# untitled.net
KiCad netlist of a schematic drawn in EAGLE
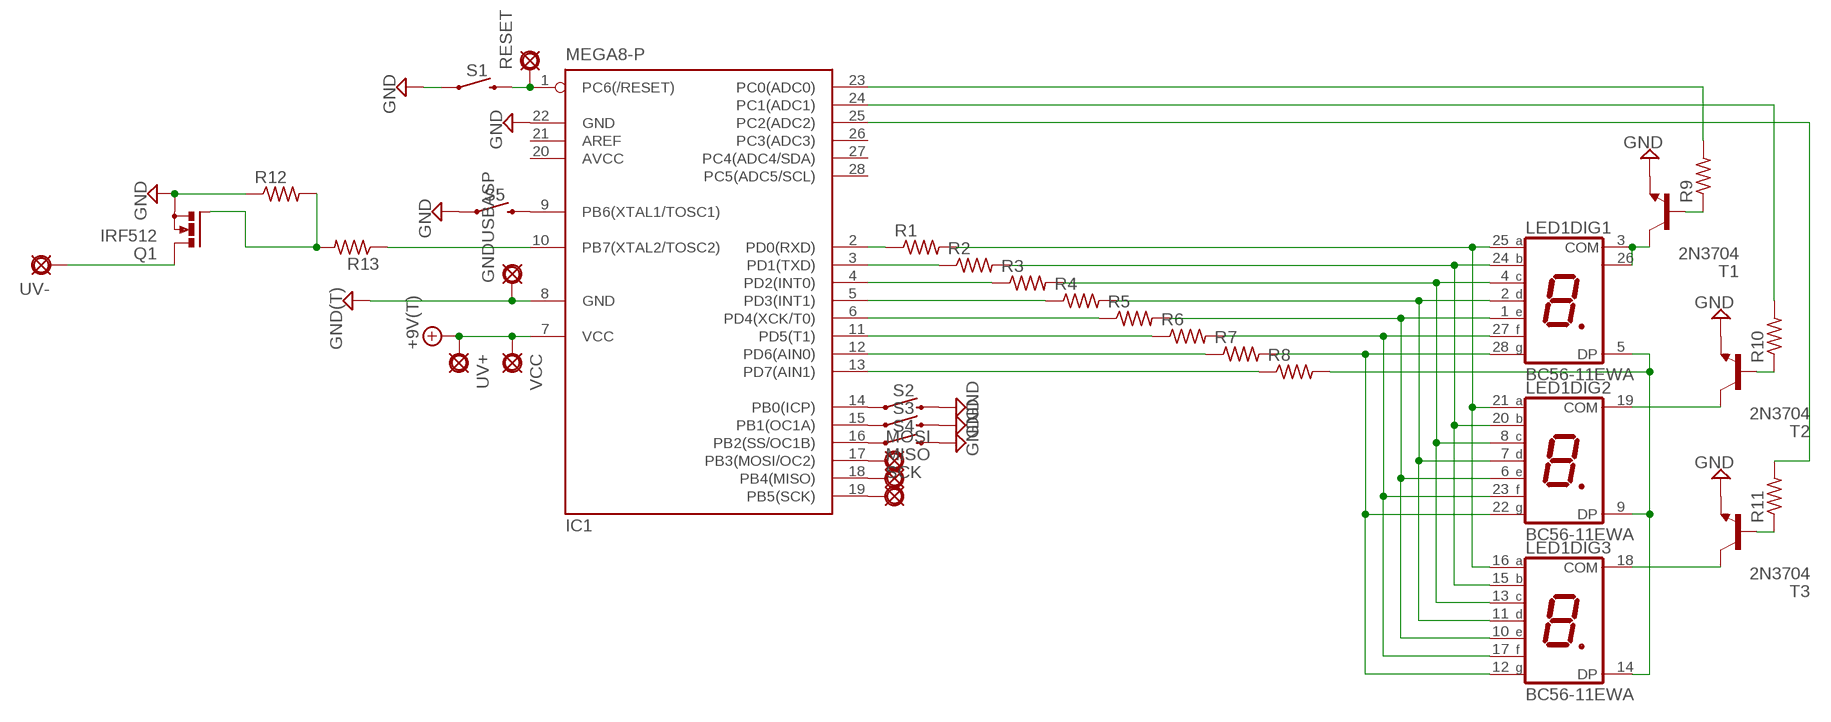
[diagram p0: schematic, sheet 1]

(export (version "E")
  (design (tool "Eeschema 10.0.6"))
  (components
    (comp (ref "+9V1")
      (value "+9V(T)")
      (footprint "eagle-import:SQUARE")
      (libsource (lib "eagle-import") (part "+9V(T)"))
    )
    (comp (ref "GND1")
      (value "GND(T)")
      (footprint "eagle-import:SQUARE")
      (libsource (lib "eagle-import") (part "GND(T)"))
    )
    (comp (ref "GNDUSBASP")
      (value "PAD")
      (footprint "eagle-import:SQUARE")
      (libsource (lib "eagle-import") (part "PAD"))
    )
    (comp (ref "IC1")
      (value "MEGA8-P")
      (footprint "eagle-import:DIL28-3")
      (libsource (lib "eagle-import") (part "MEGA8-P"))
    )
    (comp (ref "LED1")
      (value "BC56-11EWA")
      (footprint "eagle-import:BA_BC56")
      (libsource (lib "eagle-import") (part "B?56-11WACE"))
    )
    (comp (ref "MISO")
      (value "PAD")
      (footprint "eagle-import:SQUARE")
      (libsource (lib "eagle-import") (part "PAD"))
    )
    (comp (ref "MOSI")
      (value "PAD")
      (footprint "eagle-import:SQUARE")
      (libsource (lib "eagle-import") (part "PAD"))
    )
    (comp (ref "Q1")
      (value "IRF512")
      (footprint "eagle-import:TO220BV")
      (libsource (lib "eagle-import") (part "IRF512"))
    )
    (comp (ref "R1")
      (value "6MM.3")
      (footprint "eagle-import:R0207_3")
      (libsource (lib "eagle-import") (part "6MM.3"))
    )
    (comp (ref "R2")
      (value "6MM.3")
      (footprint "eagle-import:R0207_3")
      (libsource (lib "eagle-import") (part "6MM.3"))
    )
    (comp (ref "R3")
      (value "6MM.3")
      (footprint "eagle-import:R0207_3")
      (libsource (lib "eagle-import") (part "6MM.3"))
    )
    (comp (ref "R4")
      (value "6MM.3")
      (footprint "eagle-import:R0207_3")
      (libsource (lib "eagle-import") (part "6MM.3"))
    )
    (comp (ref "R5")
      (value "6MM.3")
      (footprint "eagle-import:R0207_3")
      (libsource (lib "eagle-import") (part "6MM.3"))
    )
    (comp (ref "R6")
      (value "6MM.3")
      (footprint "eagle-import:R0207_3")
      (libsource (lib "eagle-import") (part "6MM.3"))
    )
    (comp (ref "R7")
      (value "6MM.3")
      (footprint "eagle-import:R0207_3")
      (libsource (lib "eagle-import") (part "6MM.3"))
    )
    (comp (ref "R8")
      (value "6MM.3")
      (footprint "eagle-import:R0207_3")
      (libsource (lib "eagle-import") (part "6MM.3"))
    )
    (comp (ref "R9")
      (value "6MM.3")
      (footprint "eagle-import:R0207_3")
      (libsource (lib "eagle-import") (part "6MM.3"))
    )
    (comp (ref "R10")
      (value "6MM.3")
      (footprint "eagle-import:R0207_3")
      (libsource (lib "eagle-import") (part "6MM.3"))
    )
    (comp (ref "R11")
      (value "6MM.3")
      (footprint "eagle-import:R0207_3")
      (libsource (lib "eagle-import") (part "6MM.3"))
    )
    (comp (ref "R12")
      (value "6MM.3")
      (footprint "eagle-import:R0207_3")
      (libsource (lib "eagle-import") (part "6MM.3"))
    )
    (comp (ref "R13")
      (value "6MM.3")
      (footprint "eagle-import:R0207_3")
      (libsource (lib "eagle-import") (part "6MM.3"))
    )
    (comp (ref "RESET")
      (value "PAD")
      (footprint "eagle-import:SQUARE")
      (libsource (lib "eagle-import") (part "PAD"))
    )
    (comp (ref "S1")
      (value "MOMENTARY-SWITCH-SPST-PTH-6.0MM")
      (footprint "eagle-import:TACTILE_SWITCH_PTH_6.0MM")
      (libsource (lib "eagle-import") (part "MOMENTARY-SWITCH-SPST-PTH-6.0MM"))
    )
    (comp (ref "S2")
      (value "MOMENTARY-SWITCH-SPST-PTH-6.0MM")
      (footprint "eagle-import:TACTILE_SWITCH_PTH_6.0MM")
      (libsource (lib "eagle-import") (part "MOMENTARY-SWITCH-SPST-PTH-6.0MM"))
    )
    (comp (ref "S3")
      (value "MOMENTARY-SWITCH-SPST-PTH-6.0MM")
      (footprint "eagle-import:TACTILE_SWITCH_PTH_6.0MM")
      (libsource (lib "eagle-import") (part "MOMENTARY-SWITCH-SPST-PTH-6.0MM"))
    )
    (comp (ref "S4")
      (value "MOMENTARY-SWITCH-SPST-PTH-6.0MM")
      (footprint "eagle-import:TACTILE_SWITCH_PTH_6.0MM")
      (libsource (lib "eagle-import") (part "MOMENTARY-SWITCH-SPST-PTH-6.0MM"))
    )
    (comp (ref "S5")
      (value "MOMENTARY-SWITCH-SPST-PTH-6.0MM")
      (footprint "eagle-import:TACTILE_SWITCH_PTH_6.0MM")
      (libsource (lib "eagle-import") (part "MOMENTARY-SWITCH-SPST-PTH-6.0MM"))
    )
    (comp (ref "SCK")
      (value "PAD")
      (footprint "eagle-import:SQUARE")
      (libsource (lib "eagle-import") (part "PAD"))
    )
    (comp (ref "T1")
      (value "2N3704")
      (footprint "eagle-import:TO92")
      (libsource (lib "eagle-import") (part "2N3704"))
    )
    (comp (ref "T2")
      (value "2N3704")
      (footprint "eagle-import:TO92")
      (libsource (lib "eagle-import") (part "2N3704"))
    )
    (comp (ref "T3")
      (value "2N3704")
      (footprint "eagle-import:TO92")
      (libsource (lib "eagle-import") (part "2N3704"))
    )
    (comp (ref "UV+")
      (value "PAD")
      (footprint "eagle-import:SQUARE")
      (libsource (lib "eagle-import") (part "PAD"))
    )
    (comp (ref "UV-")
      (value "PAD")
      (footprint "eagle-import:SQUARE")
      (libsource (lib "eagle-import") (part "PAD"))
    )
    (comp (ref "VCC")
      (value "PAD")
      (footprint "eagle-import:SQUARE")
      (libsource (lib "eagle-import") (part "PAD"))
    )
  )
  (nets
    (net (code "1") (name "+9V(T)") (class "Default")
      (node (ref "+9V1") (pin "1") (pinfunction "+9V_1") (pintype "power_in"))
      (node (ref "IC1") (pin "7") (pinfunction "VCC_7") (pintype "power_in"))
      (node (ref "UV+") (pin "1") (pinfunction "PAD_1") (pintype "passive"))
      (node (ref "VCC") (pin "1") (pinfunction "PAD_1") (pintype "passive"))
    )
    (net (code "2") (name "/AVCC") (class "Default")
      (node (ref "IC1") (pin "20") (pinfunction "AVCC_20") (pintype "power_in"))
    )
    (net (code "3") (name "GND") (class "Default")
      (node (ref "GND1") (pin "1") (pinfunction "GND_1") (pintype "power_in"))
      (node (ref "GNDUSBASP") (pin "1") (pinfunction "PAD_1") (pintype "passive"))
      (node (ref "IC1") (pin "22") (pinfunction "GND_22") (pintype "power_in"))
      (node (ref "IC1") (pin "8") (pinfunction "GND_8") (pintype "power_in"))
      (node (ref "Q1") (pin "S") (pinfunction "S_S") (pintype "passive"))
      (node (ref "R12") (pin "1") (pinfunction "1_1") (pintype "passive"))
      (node (ref "S1") (pin "1") (pinfunction "1_1") (pintype "passive"))
      (node (ref "S2") (pin "3") (pinfunction "2_3") (pintype "passive"))
      (node (ref "S3") (pin "3") (pinfunction "2_3") (pintype "passive"))
      (node (ref "S4") (pin "3") (pinfunction "2_3") (pintype "passive"))
      (node (ref "S5") (pin "1") (pinfunction "1_1") (pintype "passive"))
      (node (ref "T1") (pin "3") (pinfunction "E_3") (pintype "passive"))
      (node (ref "T2") (pin "3") (pinfunction "E_3") (pintype "passive"))
      (node (ref "T3") (pin "3") (pinfunction "E_3") (pintype "passive"))
    )
    (net (code "4") (name "Net-(IC1-PB0(ICP))") (class "Default")
      (node (ref "IC1") (pin "14") (pinfunction "PB0(ICP)_14") (pintype "bidirectional"))
      (node (ref "S2") (pin "1") (pinfunction "1_1") (pintype "passive"))
    )
    (net (code "5") (name "Net-(IC1-PB1(OC1A))") (class "Default")
      (node (ref "IC1") (pin "15") (pinfunction "PB1(OC1A)_15") (pintype "bidirectional"))
      (node (ref "S3") (pin "1") (pinfunction "1_1") (pintype "passive"))
    )
    (net (code "6") (name "Net-(IC1-PB2(SS{slash}OC1B))") (class "Default")
      (node (ref "IC1") (pin "16") (pinfunction "PB2(SS/OC1B)_16") (pintype "bidirectional"))
      (node (ref "S4") (pin "1") (pinfunction "1_1") (pintype "passive"))
    )
    (net (code "7") (name "Net-(IC1-PB3(MOSI{slash}OC2))") (class "Default")
      (node (ref "IC1") (pin "17") (pinfunction "PB3(MOSI/OC2)_17") (pintype "bidirectional"))
      (node (ref "MOSI") (pin "1") (pinfunction "PAD_1") (pintype "passive"))
    )
    (net (code "8") (name "Net-(IC1-PB4(MISO))") (class "Default")
      (node (ref "IC1") (pin "18") (pinfunction "PB4(MISO)_18") (pintype "bidirectional"))
      (node (ref "MISO") (pin "1") (pinfunction "PAD_1") (pintype "passive"))
    )
    (net (code "9") (name "Net-(IC1-PB5(SCK))") (class "Default")
      (node (ref "IC1") (pin "19") (pinfunction "PB5(SCK)_19") (pintype "bidirectional"))
      (node (ref "SCK") (pin "1") (pinfunction "PAD_1") (pintype "passive"))
    )
    (net (code "10") (name "Net-(IC1-PB6(XTAL1{slash}TOSC1))") (class "Default")
      (node (ref "IC1") (pin "9") (pinfunction "PB6(XTAL1/TOSC1)_9") (pintype "bidirectional"))
      (node (ref "S5") (pin "3") (pinfunction "2_3") (pintype "passive"))
    )
    (net (code "11") (name "Net-(IC1-PB7(XTAL2{slash}TOSC2))") (class "Default")
      (node (ref "IC1") (pin "10") (pinfunction "PB7(XTAL2/TOSC2)_10") (pintype "bidirectional"))
      (node (ref "R13") (pin "1") (pinfunction "1_1") (pintype "passive"))
    )
    (net (code "12") (name "Net-(IC1-PC0(ADC0))") (class "Default")
      (node (ref "IC1") (pin "23") (pinfunction "PC0(ADC0)_23") (pintype "bidirectional"))
      (node (ref "R9") (pin "2") (pinfunction "2_2") (pintype "passive"))
    )
    (net (code "13") (name "Net-(IC1-PC1(ADC1))") (class "Default")
      (node (ref "IC1") (pin "24") (pinfunction "PC1(ADC1)_24") (pintype "bidirectional"))
      (node (ref "R10") (pin "2") (pinfunction "2_2") (pintype "passive"))
    )
    (net (code "14") (name "Net-(IC1-PC2(ADC2))") (class "Default")
      (node (ref "IC1") (pin "25") (pinfunction "PC2(ADC2)_25") (pintype "bidirectional"))
      (node (ref "R11") (pin "2") (pinfunction "2_2") (pintype "passive"))
    )
    (net (code "15") (name "Net-(IC1-PC6({slash}RESET))") (class "Default")
      (node (ref "IC1") (pin "1") (pinfunction "PC6(/RESET)_1") (pintype "bidirectional"))
      (node (ref "RESET") (pin "1") (pinfunction "PAD_1") (pintype "passive"))
      (node (ref "S1") (pin "3") (pinfunction "2_3") (pintype "passive"))
    )
    (net (code "16") (name "Net-(IC1-PD0(RXD))") (class "Default")
      (node (ref "IC1") (pin "2") (pinfunction "PD0(RXD)_2") (pintype "bidirectional"))
      (node (ref "R1") (pin "1") (pinfunction "1_1") (pintype "passive"))
    )
    (net (code "17") (name "Net-(IC1-PD1(TXD))") (class "Default")
      (node (ref "IC1") (pin "3") (pinfunction "PD1(TXD)_3") (pintype "bidirectional"))
      (node (ref "R2") (pin "1") (pinfunction "1_1") (pintype "passive"))
    )
    (net (code "18") (name "Net-(IC1-PD2(INT0))") (class "Default")
      (node (ref "IC1") (pin "4") (pinfunction "PD2(INT0)_4") (pintype "bidirectional"))
      (node (ref "R3") (pin "1") (pinfunction "1_1") (pintype "passive"))
    )
    (net (code "19") (name "Net-(IC1-PD3(INT1))") (class "Default")
      (node (ref "IC1") (pin "5") (pinfunction "PD3(INT1)_5") (pintype "bidirectional"))
      (node (ref "R4") (pin "1") (pinfunction "1_1") (pintype "passive"))
    )
    (net (code "20") (name "Net-(IC1-PD4(XCK{slash}T0))") (class "Default")
      (node (ref "IC1") (pin "6") (pinfunction "PD4(XCK/T0)_6") (pintype "bidirectional"))
      (node (ref "R5") (pin "1") (pinfunction "1_1") (pintype "passive"))
    )
    (net (code "21") (name "Net-(IC1-PD5(T1))") (class "Default")
      (node (ref "IC1") (pin "11") (pinfunction "PD5(T1)_11") (pintype "bidirectional"))
      (node (ref "R6") (pin "1") (pinfunction "1_1") (pintype "passive"))
    )
    (net (code "22") (name "Net-(IC1-PD6(AIN0))") (class "Default")
      (node (ref "IC1") (pin "12") (pinfunction "PD6(AIN0)_12") (pintype "bidirectional"))
      (node (ref "R7") (pin "1") (pinfunction "1_1") (pintype "passive"))
    )
    (net (code "23") (name "Net-(IC1-PD7(AIN1))") (class "Default")
      (node (ref "IC1") (pin "13") (pinfunction "PD7(AIN1)_13") (pintype "bidirectional"))
      (node (ref "R8") (pin "1") (pinfunction "1_1") (pintype "passive"))
    )
    (net (code "24") (name "Net-(LED1A-A)") (class "Default")
      (node (ref "LED1") (pin "16") (pinfunction "A_16") (pintype "passive"))
      (node (ref "LED1") (pin "21") (pinfunction "A_21") (pintype "passive"))
      (node (ref "LED1") (pin "25") (pinfunction "A_25") (pintype "passive"))
      (node (ref "R1") (pin "2") (pinfunction "2_2") (pintype "passive"))
    )
    (net (code "25") (name "Net-(LED1A-B)") (class "Default")
      (node (ref "LED1") (pin "15") (pinfunction "B_15") (pintype "passive"))
      (node (ref "LED1") (pin "20") (pinfunction "B_20") (pintype "passive"))
      (node (ref "LED1") (pin "24") (pinfunction "B_24") (pintype "passive"))
      (node (ref "R2") (pin "2") (pinfunction "2_2") (pintype "passive"))
    )
    (net (code "26") (name "Net-(LED1A-C)") (class "Default")
      (node (ref "LED1") (pin "13") (pinfunction "C_13") (pintype "passive"))
      (node (ref "LED1") (pin "4") (pinfunction "C_4") (pintype "passive"))
      (node (ref "LED1") (pin "8") (pinfunction "C_8") (pintype "passive"))
      (node (ref "R3") (pin "2") (pinfunction "2_2") (pintype "passive"))
    )
    (net (code "27") (name "Net-(LED1A-D)") (class "Default")
      (node (ref "LED1") (pin "11") (pinfunction "D_11") (pintype "passive"))
      (node (ref "LED1") (pin "2") (pinfunction "D_2") (pintype "passive"))
      (node (ref "LED1") (pin "7") (pinfunction "D_7") (pintype "passive"))
      (node (ref "R4") (pin "2") (pinfunction "2_2") (pintype "passive"))
    )
    (net (code "28") (name "Net-(LED1A-DP)") (class "Default")
      (node (ref "LED1") (pin "14") (pinfunction "DP_14") (pintype "passive"))
      (node (ref "LED1") (pin "5") (pinfunction "DP_5") (pintype "passive"))
      (node (ref "LED1") (pin "9") (pinfunction "DP_9") (pintype "passive"))
      (node (ref "R8") (pin "2") (pinfunction "2_2") (pintype "passive"))
    )
    (net (code "29") (name "Net-(LED1A-E)") (class "Default")
      (node (ref "LED1") (pin "1") (pinfunction "E_1") (pintype "passive"))
      (node (ref "LED1") (pin "10") (pinfunction "E_10") (pintype "passive"))
      (node (ref "LED1") (pin "6") (pinfunction "E_6") (pintype "passive"))
      (node (ref "R5") (pin "2") (pinfunction "2_2") (pintype "passive"))
    )
    (net (code "30") (name "Net-(LED1A-F)") (class "Default")
      (node (ref "LED1") (pin "17") (pinfunction "F_17") (pintype "passive"))
      (node (ref "LED1") (pin "23") (pinfunction "F_23") (pintype "passive"))
      (node (ref "LED1") (pin "27") (pinfunction "F_27") (pintype "passive"))
      (node (ref "R6") (pin "2") (pinfunction "2_2") (pintype "passive"))
    )
    (net (code "31") (name "Net-(LED1A-G)") (class "Default")
      (node (ref "LED1") (pin "12") (pinfunction "G_12") (pintype "passive"))
      (node (ref "LED1") (pin "22") (pinfunction "G_22") (pintype "passive"))
      (node (ref "LED1") (pin "28") (pinfunction "G_28") (pintype "passive"))
      (node (ref "R7") (pin "2") (pinfunction "2_2") (pintype "passive"))
    )
    (net (code "32") (name "Net-(LED1B-COM)") (class "Default")
      (node (ref "LED1") (pin "19") (pinfunction "COM_19") (pintype "passive"))
      (node (ref "T2") (pin "2") (pinfunction "C_2") (pintype "passive"))
    )
    (net (code "33") (name "Net-(LED1C-COM)") (class "Default")
      (node (ref "LED1") (pin "18") (pinfunction "COM_18") (pintype "passive"))
      (node (ref "T3") (pin "2") (pinfunction "C_2") (pintype "passive"))
    )
    (net (code "34") (name "Net-(Q1-PadG)") (class "Default")
      (node (ref "Q1") (pin "G") (pinfunction "G_G") (pintype "passive"))
      (node (ref "R12") (pin "2") (pinfunction "2_2") (pintype "passive"))
      (node (ref "R13") (pin "2") (pinfunction "2_2") (pintype "passive"))
    )
    (net (code "35") (name "Net-(T1-B)") (class "Default")
      (node (ref "R9") (pin "1") (pinfunction "1_1") (pintype "passive"))
      (node (ref "T1") (pin "1") (pinfunction "B_1") (pintype "passive"))
    )
    (net (code "36") (name "Net-(T1-C)") (class "Default")
      (node (ref "LED1") (pin "26") (pinfunction "COM_26") (pintype "passive"))
      (node (ref "LED1") (pin "3") (pinfunction "COM_3") (pintype "passive"))
      (node (ref "T1") (pin "2") (pinfunction "C_2") (pintype "passive"))
    )
    (net (code "37") (name "Net-(T2-B)") (class "Default")
      (node (ref "R10") (pin "1") (pinfunction "1_1") (pintype "passive"))
      (node (ref "T2") (pin "1") (pinfunction "B_1") (pintype "passive"))
    )
    (net (code "38") (name "Net-(T3-B)") (class "Default")
      (node (ref "R11") (pin "1") (pinfunction "1_1") (pintype "passive"))
      (node (ref "T3") (pin "1") (pinfunction "B_1") (pintype "passive"))
    )
    (net (code "39") (name "Net-(UV--PAD)") (class "Default")
      (node (ref "Q1") (pin "D") (pinfunction "D_D") (pintype "passive"))
      (node (ref "UV-") (pin "1") (pinfunction "PAD_1") (pintype "passive"))
    )
    (net (code "40") (name "unconnected-(IC1-AREF-Pad21)") (class "Default")
      (node (ref "IC1") (pin "21") (pinfunction "AREF_21") (pintype "passive"))
    )
    (net (code "41") (name "unconnected-(IC1-PC3(ADC3)-Pad26)") (class "Default")
      (node (ref "IC1") (pin "26") (pinfunction "PC3(ADC3)_26") (pintype "bidirectional"))
    )
    (net (code "42") (name "unconnected-(IC1-PC4(ADC4{slash}SDA)-Pad27)") (class "Default")
      (node (ref "IC1") (pin "27") (pinfunction "PC4(ADC4/SDA)_27") (pintype "bidirectional"))
    )
    (net (code "43") (name "unconnected-(IC1-PC5(ADC5{slash}SCL)-Pad28)") (class "Default")
      (node (ref "IC1") (pin "28") (pinfunction "PC5(ADC5/SCL)_28") (pintype "bidirectional"))
    )
  )
)
